# Nanocopter.net
KiCad netlist of a schematic drawn in EAGLE
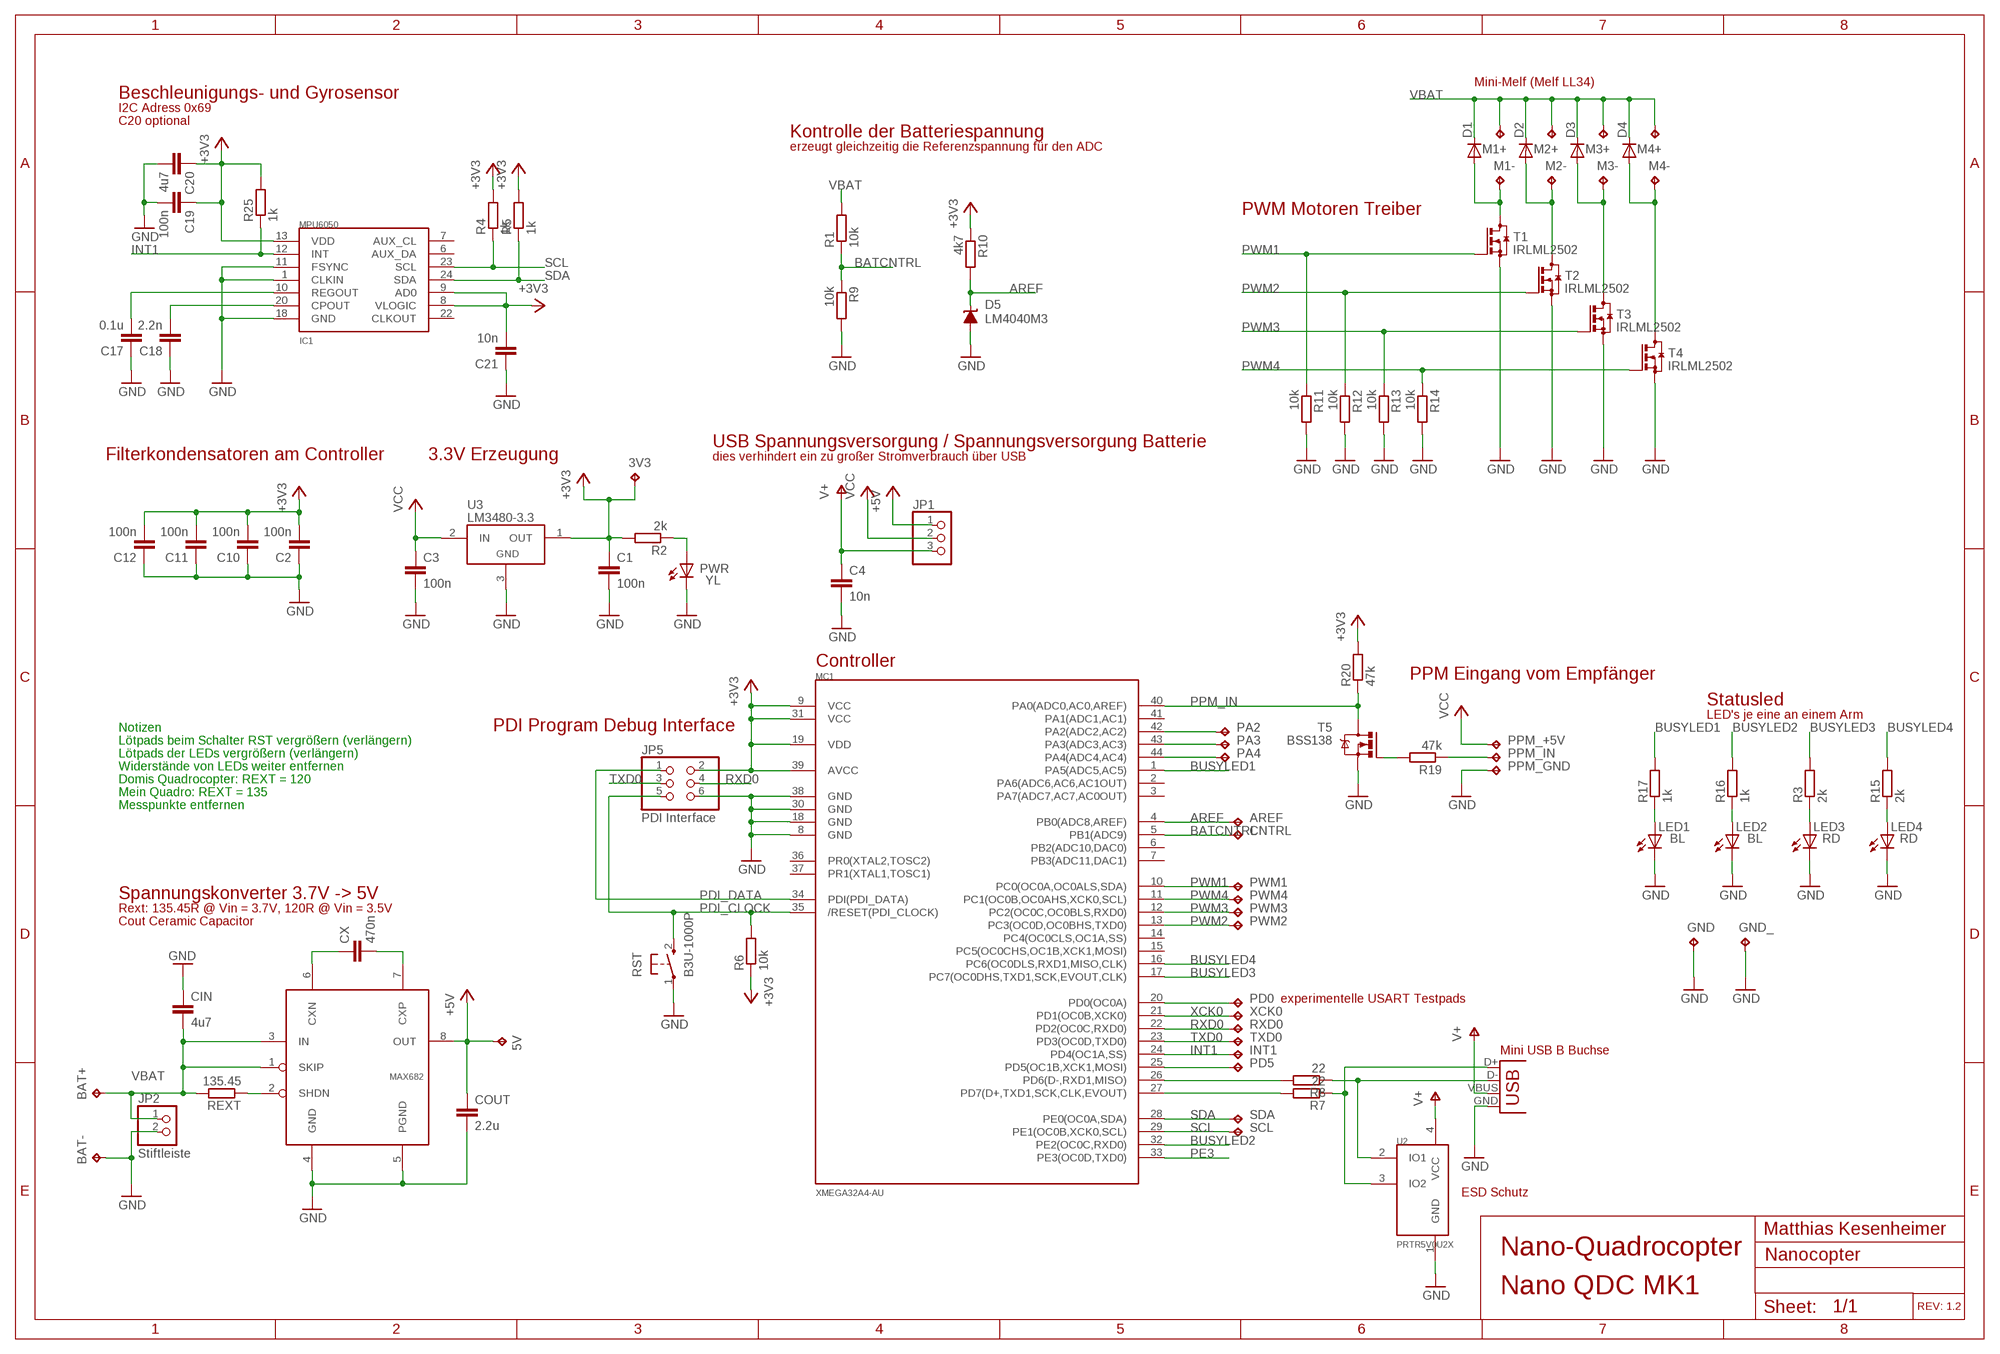
[diagram p0: schematic, sheet 1]

(export (version "E")
  (design (tool "Eeschema 10.0.6"))
  (components
    (comp (ref "3V3")
      (value "TPTP12SQ")
      (footprint "eagle-import:TP12SQ")
      (libsource (lib "eagle-import") (part "TPTP12SQ"))
    )
    (comp (ref "5V")
      (value "TPTP12SQ")
      (footprint "eagle-import:TP12SQ")
      (libsource (lib "eagle-import") (part "TPTP12SQ"))
    )
    (comp (ref "AREF")
      (value "TPTP10SQ")
      (footprint "eagle-import:TP10SQ")
      (libsource (lib "eagle-import") (part "TPTP10SQ"))
    )
    (comp (ref "BAT+")
      (value "TPTP12SQ")
      (footprint "eagle-import:TP12SQ")
      (libsource (lib "eagle-import") (part "TPTP12SQ"))
    )
    (comp (ref "BAT-")
      (value "TPTP12SQ")
      (footprint "eagle-import:TP12SQ")
      (libsource (lib "eagle-import") (part "TPTP12SQ"))
    )
    (comp (ref "C1")
      (value "100n")
      (footprint "eagle-import:C0603")
      (libsource (lib "eagle-import") (part "C-EUC0603"))
    )
    (comp (ref "C2")
      (value "100n")
      (footprint "eagle-import:C0603")
      (libsource (lib "eagle-import") (part "C-EUC0603"))
    )
    (comp (ref "C3")
      (value "100n")
      (footprint "eagle-import:C0603")
      (libsource (lib "eagle-import") (part "C-EUC0603"))
    )
    (comp (ref "C4")
      (value "10n")
      (footprint "eagle-import:C0603")
      (libsource (lib "eagle-import") (part "C-EUC0603"))
    )
    (comp (ref "C10")
      (value "100n")
      (footprint "eagle-import:C0603")
      (libsource (lib "eagle-import") (part "C-EUC0603"))
    )
    (comp (ref "C11")
      (value "100n")
      (footprint "eagle-import:C0603")
      (libsource (lib "eagle-import") (part "C-EUC0603"))
    )
    (comp (ref "C12")
      (value "100n")
      (footprint "eagle-import:C0603")
      (libsource (lib "eagle-import") (part "C-EUC0603"))
    )
    (comp (ref "C17")
      (value "0.1u")
      (footprint "eagle-import:C0603")
      (libsource (lib "eagle-import") (part "C-EUC0603"))
    )
    (comp (ref "C18")
      (value "2.2n")
      (footprint "eagle-import:C0603")
      (libsource (lib "eagle-import") (part "C-EUC0603"))
    )
    (comp (ref "C19")
      (value "100n")
      (footprint "eagle-import:C0603")
      (libsource (lib "eagle-import") (part "C-EUC0603"))
    )
    (comp (ref "C20")
      (value "4u7")
      (footprint "eagle-import:C0603")
      (libsource (lib "eagle-import") (part "C-EUC0603"))
    )
    (comp (ref "C21")
      (value "10n")
      (footprint "eagle-import:C0603")
      (libsource (lib "eagle-import") (part "C-EUC0603"))
    )
    (comp (ref "CIN")
      (value "4u7")
      (footprint "eagle-import:C1206")
      (libsource (lib "eagle-import") (part "C-EUC1206"))
    )
    (comp (ref "CNTRL")
      (value "TPTP10SQ")
      (footprint "eagle-import:TP10SQ")
      (libsource (lib "eagle-import") (part "TPTP10SQ"))
    )
    (comp (ref "COUT")
      (value "2.2u")
      (footprint "eagle-import:C1206")
      (libsource (lib "eagle-import") (part "C-EUC1206"))
    )
    (comp (ref "CX")
      (value "470n")
      (footprint "eagle-import:C0603")
      (libsource (lib "eagle-import") (part "C-EUC0603"))
    )
    (comp (ref "D1")
      (value "DIODE-MINIMELF")
      (footprint "eagle-import:MINIMELF")
      (libsource (lib "eagle-import") (part "DIODE-MINIMELF"))
    )
    (comp (ref "D2")
      (value "DIODE-MINIMELF")
      (footprint "eagle-import:MINIMELF")
      (libsource (lib "eagle-import") (part "DIODE-MINIMELF"))
    )
    (comp (ref "D3")
      (value "DIODE-MINIMELF")
      (footprint "eagle-import:MINIMELF")
      (libsource (lib "eagle-import") (part "DIODE-MINIMELF"))
    )
    (comp (ref "D4")
      (value "DIODE-MINIMELF")
      (footprint "eagle-import:MINIMELF")
      (libsource (lib "eagle-import") (part "DIODE-MINIMELF"))
    )
    (comp (ref "D5")
      (value "LM4040M3")
      (footprint "eagle-import:SOT-23")
      (libsource (lib "eagle-import") (part "LM4040M3"))
    )
    (comp (ref "GND")
      (value "TPTP12SQ")
      (footprint "eagle-import:TP12SQ")
      (libsource (lib "eagle-import") (part "TPTP12SQ"))
    )
    (comp (ref "GND_")
      (value "TPTP12SQ")
      (footprint "eagle-import:TP12SQ")
      (libsource (lib "eagle-import") (part "TPTP12SQ"))
    )
    (comp (ref "IC1")
      (value "MPU6050")
      (footprint "eagle-import:QFN-24")
      (libsource (lib "eagle-import") (part "MPU6050"))
    )
    (comp (ref "INT1")
      (value "TPTP10SQ")
      (footprint "eagle-import:TP10SQ")
      (libsource (lib "eagle-import") (part "TPTP10SQ"))
    )
    (comp (ref "JP1")
      (value "PINHD-1X3")
      (footprint "eagle-import:1X03")
      (libsource (lib "eagle-import") (part "PINHD-1X3"))
    )
    (comp (ref "JP2")
      (value "Stiftleiste")
      (footprint "eagle-import:1X02")
      (libsource (lib "eagle-import") (part "PINHD-1X2"))
    )
    (comp (ref "JP5")
      (value "PDI Interface")
      (footprint "eagle-import:2X03")
      (libsource (lib "eagle-import") (part "PINHD-2X3"))
    )
    (comp (ref "LED1")
      (value "BL")
      (footprint "eagle-import:CHIPLED_0603")
      (libsource (lib "eagle-import") (part "LEDCHIPLED_0603"))
    )
    (comp (ref "LED2")
      (value "BL")
      (footprint "eagle-import:CHIPLED_0603")
      (libsource (lib "eagle-import") (part "LEDCHIPLED_0603"))
    )
    (comp (ref "LED3")
      (value "RD")
      (footprint "eagle-import:CHIPLED_0603")
      (libsource (lib "eagle-import") (part "LEDCHIPLED_0603"))
    )
    (comp (ref "LED4")
      (value "RD")
      (footprint "eagle-import:CHIPLED_0603")
      (libsource (lib "eagle-import") (part "LEDCHIPLED_0603"))
    )
    (comp (ref "M1+")
      (value "TPTP15SQ")
      (footprint "eagle-import:TP15SQ")
      (libsource (lib "eagle-import") (part "TPTP15SQ"))
    )
    (comp (ref "M1-")
      (value "TPTP15SQ")
      (footprint "eagle-import:TP15SQ")
      (libsource (lib "eagle-import") (part "TPTP15SQ"))
    )
    (comp (ref "M2+")
      (value "TPTP15SQ")
      (footprint "eagle-import:TP15SQ")
      (libsource (lib "eagle-import") (part "TPTP15SQ"))
    )
    (comp (ref "M2-")
      (value "TPTP15SQ")
      (footprint "eagle-import:TP15SQ")
      (libsource (lib "eagle-import") (part "TPTP15SQ"))
    )
    (comp (ref "M3+")
      (value "TPTP15SQ")
      (footprint "eagle-import:TP15SQ")
      (libsource (lib "eagle-import") (part "TPTP15SQ"))
    )
    (comp (ref "M3-")
      (value "TPTP15SQ")
      (footprint "eagle-import:TP15SQ")
      (libsource (lib "eagle-import") (part "TPTP15SQ"))
    )
    (comp (ref "M4+")
      (value "TPTP15SQ")
      (footprint "eagle-import:TP15SQ")
      (libsource (lib "eagle-import") (part "TPTP15SQ"))
    )
    (comp (ref "M4-")
      (value "TPTP15SQ")
      (footprint "eagle-import:TP15SQ")
      (libsource (lib "eagle-import") (part "TPTP15SQ"))
    )
    (comp (ref "MC1")
      (value "XMEGA32A4-AU")
      (footprint "eagle-import:TQFP44")
      (libsource (lib "eagle-import") (part "XMEGA32A4-AU"))
    )
    (comp (ref "PA2")
      (value "TPTP10SQ")
      (footprint "eagle-import:TP10SQ")
      (libsource (lib "eagle-import") (part "TPTP10SQ"))
    )
    (comp (ref "PA3")
      (value "TPTP10SQ")
      (footprint "eagle-import:TP10SQ")
      (libsource (lib "eagle-import") (part "TPTP10SQ"))
    )
    (comp (ref "PA4")
      (value "TPTP10SQ")
      (footprint "eagle-import:TP10SQ")
      (libsource (lib "eagle-import") (part "TPTP10SQ"))
    )
    (comp (ref "PD0")
      (value "TPTP10SQ")
      (footprint "eagle-import:TP10SQ")
      (libsource (lib "eagle-import") (part "TPTP10SQ"))
    )
    (comp (ref "PD5")
      (value "TPTP10SQ")
      (footprint "eagle-import:TP10SQ")
      (libsource (lib "eagle-import") (part "TPTP10SQ"))
    )
    (comp (ref "PPM_+5V")
      (value "TPTP10SQ")
      (footprint "eagle-import:TP10SQ")
      (libsource (lib "eagle-import") (part "TPTP10SQ"))
    )
    (comp (ref "PPM_GND")
      (value "TPTP10SQ")
      (footprint "eagle-import:TP10SQ")
      (libsource (lib "eagle-import") (part "TPTP10SQ"))
    )
    (comp (ref "PPM_IN")
      (value "TPTP10SQ")
      (footprint "eagle-import:TP10SQ")
      (libsource (lib "eagle-import") (part "TPTP10SQ"))
    )
    (comp (ref "PWM1")
      (value "TPTP10SQ")
      (footprint "eagle-import:TP10SQ")
      (libsource (lib "eagle-import") (part "TPTP10SQ"))
    )
    (comp (ref "PWM2")
      (value "TPTP10SQ")
      (footprint "eagle-import:TP10SQ")
      (libsource (lib "eagle-import") (part "TPTP10SQ"))
    )
    (comp (ref "PWM3")
      (value "TPTP10SQ")
      (footprint "eagle-import:TP10SQ")
      (libsource (lib "eagle-import") (part "TPTP10SQ"))
    )
    (comp (ref "PWM4")
      (value "TPTP10SQ")
      (footprint "eagle-import:TP10SQ")
      (libsource (lib "eagle-import") (part "TPTP10SQ"))
    )
    (comp (ref "PWR")
      (value "YL")
      (footprint "eagle-import:CHIPLED_0603")
      (libsource (lib "eagle-import") (part "LEDCHIPLED_0603"))
    )
    (comp (ref "R1")
      (value "10k")
      (footprint "eagle-import:R0603")
      (libsource (lib "eagle-import") (part "R-EU_R0603"))
    )
    (comp (ref "R2")
      (value "2k")
      (footprint "eagle-import:R0603")
      (libsource (lib "eagle-import") (part "R-EU_R0603"))
    )
    (comp (ref "R3")
      (value "2k")
      (footprint "eagle-import:R0603")
      (libsource (lib "eagle-import") (part "R-EU_R0603"))
    )
    (comp (ref "R4")
      (value "1k")
      (footprint "eagle-import:R0603")
      (libsource (lib "eagle-import") (part "R-EU_R0603"))
    )
    (comp (ref "R5")
      (value "1k")
      (footprint "eagle-import:R0603")
      (libsource (lib "eagle-import") (part "R-EU_R0603"))
    )
    (comp (ref "R6")
      (value "10k")
      (footprint "eagle-import:R0603")
      (libsource (lib "eagle-import") (part "R-EU_R0603"))
    )
    (comp (ref "R7")
      (value "22")
      (footprint "eagle-import:R0603")
      (libsource (lib "eagle-import") (part "R-EU_R0603"))
    )
    (comp (ref "R8")
      (value "22")
      (footprint "eagle-import:R0603")
      (libsource (lib "eagle-import") (part "R-EU_R0603"))
    )
    (comp (ref "R9")
      (value "10k")
      (footprint "eagle-import:R0603")
      (libsource (lib "eagle-import") (part "R-EU_R0603"))
    )
    (comp (ref "R10")
      (value "4k7")
      (footprint "eagle-import:R0603")
      (libsource (lib "eagle-import") (part "R-EU_R0603"))
    )
    (comp (ref "R11")
      (value "10k")
      (footprint "eagle-import:R0603")
      (libsource (lib "eagle-import") (part "R-EU_R0603"))
    )
    (comp (ref "R12")
      (value "10k")
      (footprint "eagle-import:R0603")
      (libsource (lib "eagle-import") (part "R-EU_R0603"))
    )
    (comp (ref "R13")
      (value "10k")
      (footprint "eagle-import:R0603")
      (libsource (lib "eagle-import") (part "R-EU_R0603"))
    )
    (comp (ref "R14")
      (value "10k")
      (footprint "eagle-import:R0603")
      (libsource (lib "eagle-import") (part "R-EU_R0603"))
    )
    (comp (ref "R15")
      (value "2k")
      (footprint "eagle-import:R0603")
      (libsource (lib "eagle-import") (part "R-EU_R0603"))
    )
    (comp (ref "R16")
      (value "1k")
      (footprint "eagle-import:R0603")
      (libsource (lib "eagle-import") (part "R-EU_R0603"))
    )
    (comp (ref "R17")
      (value "1k")
      (footprint "eagle-import:R0603")
      (libsource (lib "eagle-import") (part "R-EU_R0603"))
    )
    (comp (ref "R19")
      (value "47k")
      (footprint "eagle-import:R0603")
      (libsource (lib "eagle-import") (part "R-EU_R0603"))
    )
    (comp (ref "R20")
      (value "47k")
      (footprint "eagle-import:R0603")
      (libsource (lib "eagle-import") (part "R-EU_R0603"))
    )
    (comp (ref "R25")
      (value "1k")
      (footprint "eagle-import:R0603")
      (libsource (lib "eagle-import") (part "R-EU_R0603"))
    )
    (comp (ref "REXT")
      (value "135.45")
      (footprint "eagle-import:R0603")
      (libsource (lib "eagle-import") (part "R-EU_R0603"))
    )
    (comp (ref "RST")
      (value "B3U-1000P")
      (footprint "eagle-import:SW_SMD")
      (libsource (lib "eagle-import") (part "B3U-1000P"))
    )
    (comp (ref "RXD0")
      (value "TPTP10SQ")
      (footprint "eagle-import:TP10SQ")
      (libsource (lib "eagle-import") (part "TPTP10SQ"))
    )
    (comp (ref "SCL")
      (value "TPTP10SQ")
      (footprint "eagle-import:TP10SQ")
      (libsource (lib "eagle-import") (part "TPTP10SQ"))
    )
    (comp (ref "SDA")
      (value "TPTP10SQ")
      (footprint "eagle-import:TP10SQ")
      (libsource (lib "eagle-import") (part "TPTP10SQ"))
    )
    (comp (ref "T1")
      (value "IRLML2502")
      (footprint "eagle-import:SOT23")
      (libsource (lib "eagle-import") (part "BSS123"))
    )
    (comp (ref "T2")
      (value "IRLML2502")
      (footprint "eagle-import:SOT23")
      (libsource (lib "eagle-import") (part "BSS123"))
    )
    (comp (ref "T3")
      (value "IRLML2502")
      (footprint "eagle-import:SOT23")
      (libsource (lib "eagle-import") (part "BSS123"))
    )
    (comp (ref "T4")
      (value "IRLML2502")
      (footprint "eagle-import:SOT23")
      (libsource (lib "eagle-import") (part "BSS123"))
    )
    (comp (ref "T5")
      (value "BSS138")
      (footprint "eagle-import:SOT23")
      (libsource (lib "eagle-import") (part "BSS138"))
    )
    (comp (ref "TXD0")
      (value "TPTP10SQ")
      (footprint "eagle-import:TP10SQ")
      (libsource (lib "eagle-import") (part "TPTP10SQ"))
    )
    (comp (ref "U1")
      (value "MAX682")
      (footprint "eagle-import:SOIC(N)8")
      (libsource (lib "eagle-import") (part "MAX682"))
    )
    (comp (ref "U2")
      (value "PRTR5V0U2X")
      (footprint "eagle-import:SOT143B")
      (libsource (lib "eagle-import") (part "PRTR5V0U2X"))
    )
    (comp (ref "U3")
      (value "LM3480-3.3")
      (footprint "eagle-import:SOT-23-3")
      (libsource (lib "eagle-import") (part "LM3480-3.3"))
    )
    (comp (ref "X1")
      (value "USBSMD")
      (footprint "eagle-import:USB-MINIB")
      (libsource (lib "eagle-import") (part "USBSMD"))
    )
    (comp (ref "XCK0")
      (value "TPTP10SQ")
      (footprint "eagle-import:TP10SQ")
      (libsource (lib "eagle-import") (part "TPTP10SQ"))
    )
  )
  (nets
    (net (code "1") (name "+3V3") (class "Default")
      (node (ref "3V3") (pin "TP") (pinfunction "TP_TP") (pintype "input"))
      (node (ref "C1") (pin "1") (pinfunction "1_1") (pintype "passive"))
      (node (ref "C10") (pin "2") (pinfunction "2_2") (pintype "passive"))
      (node (ref "C11") (pin "2") (pinfunction "2_2") (pintype "passive"))
      (node (ref "C12") (pin "2") (pinfunction "2_2") (pintype "passive"))
      (node (ref "C19") (pin "1") (pinfunction "1_1") (pintype "passive"))
      (node (ref "C2") (pin "2") (pinfunction "2_2") (pintype "passive"))
      (node (ref "C20") (pin "1") (pinfunction "1_1") (pintype "passive"))
      (node (ref "C21") (pin "2") (pinfunction "2_2") (pintype "passive"))
      (node (ref "IC1") (pin "13") (pinfunction "VDD_13") (pintype "power_in"))
      (node (ref "IC1") (pin "8") (pinfunction "VLOGIC_8") (pintype "power_in"))
      (node (ref "IC1") (pin "9") (pinfunction "AD0_9") (pintype "input"))
      (node (ref "JP5") (pin "2") (pinfunction "2_2") (pintype "passive"))
      (node (ref "MC1") (pin "19") (pinfunction "VDD_19") (pintype "power_in"))
      (node (ref "MC1") (pin "31") (pinfunction "VCC_31") (pintype "power_in"))
      (node (ref "MC1") (pin "39") (pinfunction "AVCC_39") (pintype "power_in"))
      (node (ref "MC1") (pin "9") (pinfunction "VCC_9") (pintype "power_in"))
      (node (ref "R10") (pin "1") (pinfunction "1_1") (pintype "passive"))
      (node (ref "R2") (pin "2") (pinfunction "2_2") (pintype "passive"))
      (node (ref "R20") (pin "2") (pinfunction "2_2") (pintype "passive"))
      (node (ref "R25") (pin "2") (pinfunction "2_2") (pintype "passive"))
      (node (ref "R4") (pin "2") (pinfunction "2_2") (pintype "passive"))
      (node (ref "R5") (pin "2") (pinfunction "2_2") (pintype "passive"))
      (node (ref "R6") (pin "1") (pinfunction "1_1") (pintype "passive"))
      (node (ref "U3") (pin "1") (pinfunction "OUT_1") (pintype "power_in"))
    )
    (net (code "2") (name "+5V") (class "Default")
      (node (ref "5V") (pin "TP") (pinfunction "TP_TP") (pintype "input"))
      (node (ref "COUT") (pin "1") (pinfunction "1_1") (pintype "passive"))
      (node (ref "JP1") (pin "1") (pinfunction "1_1") (pintype "passive"))
      (node (ref "U1") (pin "8") (pinfunction "OUT_8") (pintype "power_in"))
    )
    (net (code "3") (name "/AREF") (class "Default")
      (node (ref "AREF") (pin "TP") (pinfunction "TP_TP") (pintype "input"))
      (node (ref "D5") (pin "1") (pinfunction "C_1") (pintype "passive"))
      (node (ref "MC1") (pin "4") (pinfunction "PB0(ADC8,AREF)_4") (pintype "bidirectional"))
      (node (ref "R10") (pin "2") (pinfunction "2_2") (pintype "passive"))
    )
    (net (code "4") (name "/BATCNTRL") (class "Default")
      (node (ref "CNTRL") (pin "TP") (pinfunction "TP_TP") (pintype "input"))
      (node (ref "MC1") (pin "5") (pinfunction "PB1(ADC9)_5") (pintype "bidirectional"))
      (node (ref "R1") (pin "1") (pinfunction "1_1") (pintype "passive"))
      (node (ref "R9") (pin "1") (pinfunction "1_1") (pintype "passive"))
    )
    (net (code "5") (name "/BUSYLED1") (class "Default")
      (node (ref "MC1") (pin "1") (pinfunction "PA5(ADC5,AC5)_1") (pintype "bidirectional"))
      (node (ref "R17") (pin "2") (pinfunction "2_2") (pintype "passive"))
    )
    (net (code "6") (name "/BUSYLED2") (class "Default")
      (node (ref "MC1") (pin "32") (pinfunction "PE2(OC0C,RXD0)_32") (pintype "bidirectional"))
      (node (ref "R16") (pin "2") (pinfunction "2_2") (pintype "passive"))
    )
    (net (code "7") (name "/BUSYLED3") (class "Default")
      (node (ref "MC1") (pin "17") (pinfunction "PC7(OC0DHS,TXD1,SCK,EVOUT,CLK)_17") (pintype "bidirectional"))
      (node (ref "R3") (pin "2") (pinfunction "2_2") (pintype "passive"))
    )
    (net (code "8") (name "/BUSYLED4") (class "Default")
      (node (ref "MC1") (pin "16") (pinfunction "PC6(OC0DLS,RXD1,MISO,CLK)_16") (pintype "bidirectional"))
      (node (ref "R15") (pin "2") (pinfunction "2_2") (pintype "passive"))
    )
    (net (code "9") (name "/INT1") (class "Default")
      (node (ref "IC1") (pin "12") (pinfunction "INT_12") (pintype "output"))
      (node (ref "INT1") (pin "TP") (pinfunction "TP_TP") (pintype "input"))
      (node (ref "MC1") (pin "24") (pinfunction "PD4(OC1A,SS)_24") (pintype "bidirectional"))
      (node (ref "R25") (pin "1") (pinfunction "1_1") (pintype "passive"))
    )
    (net (code "10") (name "/PDI_CLOCK") (class "Default")
      (node (ref "JP5") (pin "5") (pinfunction "5_5") (pintype "passive"))
      (node (ref "MC1") (pin "35") (pinfunction "/RESET(PDI_CLOCK)_35") (pintype "bidirectional"))
      (node (ref "R6") (pin "2") (pinfunction "2_2") (pintype "passive"))
      (node (ref "RST") (pin "2") (pinfunction "2_2") (pintype "passive"))
    )
    (net (code "11") (name "/PDI_DATA") (class "Default")
      (node (ref "JP5") (pin "1") (pinfunction "1_1") (pintype "passive"))
      (node (ref "MC1") (pin "34") (pinfunction "PDI(PDI_DATA)_34") (pintype "bidirectional"))
    )
    (net (code "12") (name "/PE3") (class "Default")
      (node (ref "MC1") (pin "33") (pinfunction "PE3(OC0D,TXD0)_33") (pintype "bidirectional"))
    )
    (net (code "13") (name "/PPM_IN") (class "Default")
      (node (ref "MC1") (pin "40") (pinfunction "PA0(ADC0,AC0,AREF)_40") (pintype "bidirectional"))
      (node (ref "R20") (pin "1") (pinfunction "1_1") (pintype "passive"))
      (node (ref "T5") (pin "3") (pinfunction "D_3") (pintype "passive"))
    )
    (net (code "14") (name "/PWM1") (class "Default")
      (node (ref "MC1") (pin "10") (pinfunction "PC0(OC0A,OC0ALS,SDA)_10") (pintype "bidirectional"))
      (node (ref "PWM1") (pin "TP") (pinfunction "TP_TP") (pintype "input"))
      (node (ref "R11") (pin "1") (pinfunction "1_1") (pintype "passive"))
      (node (ref "T1") (pin "1") (pinfunction "G_1") (pintype "passive"))
    )
    (net (code "15") (name "/PWM2") (class "Default")
      (node (ref "MC1") (pin "13") (pinfunction "PC3(OC0D,OC0BHS,TXD0)_13") (pintype "bidirectional"))
      (node (ref "PWM2") (pin "TP") (pinfunction "TP_TP") (pintype "input"))
      (node (ref "R12") (pin "1") (pinfunction "1_1") (pintype "passive"))
      (node (ref "T2") (pin "1") (pinfunction "G_1") (pintype "passive"))
    )
    (net (code "16") (name "/PWM3") (class "Default")
      (node (ref "MC1") (pin "12") (pinfunction "PC2(OC0C,OC0BLS,RXD0)_12") (pintype "bidirectional"))
      (node (ref "PWM3") (pin "TP") (pinfunction "TP_TP") (pintype "input"))
      (node (ref "R13") (pin "1") (pinfunction "1_1") (pintype "passive"))
      (node (ref "T3") (pin "1") (pinfunction "G_1") (pintype "passive"))
    )
    (net (code "17") (name "/PWM4") (class "Default")
      (node (ref "MC1") (pin "11") (pinfunction "PC1(OC0B,OC0AHS,XCK0,SCL)_11") (pintype "bidirectional"))
      (node (ref "PWM4") (pin "TP") (pinfunction "TP_TP") (pintype "input"))
      (node (ref "R14") (pin "1") (pinfunction "1_1") (pintype "passive"))
      (node (ref "T4") (pin "1") (pinfunction "G_1") (pintype "passive"))
    )
    (net (code "18") (name "/RXD0") (class "Default")
      (node (ref "JP5") (pin "4") (pinfunction "4_4") (pintype "passive"))
      (node (ref "MC1") (pin "22") (pinfunction "PD2(OC0C,RXD0)_22") (pintype "bidirectional"))
      (node (ref "RXD0") (pin "TP") (pinfunction "TP_TP") (pintype "input"))
    )
    (net (code "19") (name "/SCL") (class "Default")
      (node (ref "IC1") (pin "23") (pinfunction "SCL_23") (pintype "input"))
      (node (ref "MC1") (pin "29") (pinfunction "PE1(OC0B,XCK0,SCL)_29") (pintype "bidirectional"))
      (node (ref "R4") (pin "1") (pinfunction "1_1") (pintype "passive"))
      (node (ref "SCL") (pin "TP") (pinfunction "TP_TP") (pintype "input"))
    )
    (net (code "20") (name "/SDA") (class "Default")
      (node (ref "IC1") (pin "24") (pinfunction "SDA_24") (pintype "bidirectional"))
      (node (ref "MC1") (pin "28") (pinfunction "PE0(OC0A,SDA)_28") (pintype "bidirectional"))
      (node (ref "R5") (pin "1") (pinfunction "1_1") (pintype "passive"))
      (node (ref "SDA") (pin "TP") (pinfunction "TP_TP") (pintype "input"))
    )
    (net (code "21") (name "/TXD0") (class "Default")
      (node (ref "JP5") (pin "3") (pinfunction "3_3") (pintype "passive"))
      (node (ref "MC1") (pin "23") (pinfunction "PD3(OC0D,TXD0)_23") (pintype "bidirectional"))
      (node (ref "TXD0") (pin "TP") (pinfunction "TP_TP") (pintype "input"))
    )
    (net (code "22") (name "/VBAT") (class "Default")
      (node (ref "BAT+") (pin "TP") (pinfunction "TP_TP") (pintype "input"))
      (node (ref "CIN") (pin "2") (pinfunction "2_2") (pintype "passive"))
      (node (ref "D1") (pin "C") (pinfunction "C_C") (pintype "passive"))
      (node (ref "D2") (pin "C") (pinfunction "C_C") (pintype "passive"))
      (node (ref "D3") (pin "C") (pinfunction "C_C") (pintype "passive"))
      (node (ref "D4") (pin "C") (pinfunction "C_C") (pintype "passive"))
      (node (ref "JP2") (pin "1") (pinfunction "1_1") (pintype "passive"))
      (node (ref "M1+") (pin "TP") (pinfunction "TP_TP") (pintype "input"))
      (node (ref "M2+") (pin "TP") (pinfunction "TP_TP") (pintype "input"))
      (node (ref "M3+") (pin "TP") (pinfunction "TP_TP") (pintype "input"))
      (node (ref "M4+") (pin "TP") (pinfunction "TP_TP") (pintype "input"))
      (node (ref "R1") (pin "2") (pinfunction "2_2") (pintype "passive"))
      (node (ref "REXT") (pin "2") (pinfunction "2_2") (pintype "passive"))
      (node (ref "U1") (pin "1") (pinfunction "SKIP_1") (pintype "input"))
      (node (ref "U1") (pin "3") (pinfunction "IN_3") (pintype "input"))
    )
    (net (code "23") (name "/XCK0") (class "Default")
      (node (ref "MC1") (pin "21") (pinfunction "PD1(OC0B,XCK0)_21") (pintype "bidirectional"))
      (node (ref "XCK0") (pin "TP") (pinfunction "TP_TP") (pintype "input"))
    )
    (net (code "24") (name "GND") (class "Default")
      (node (ref "BAT-") (pin "TP") (pinfunction "TP_TP") (pintype "input"))
      (node (ref "C1") (pin "2") (pinfunction "2_2") (pintype "passive"))
      (node (ref "C10") (pin "1") (pinfunction "1_1") (pintype "passive"))
      (node (ref "C11") (pin "1") (pinfunction "1_1") (pintype "passive"))
      (node (ref "C12") (pin "1") (pinfunction "1_1") (pintype "passive"))
      (node (ref "C17") (pin "1") (pinfunction "1_1") (pintype "passive"))
      (node (ref "C18") (pin "1") (pinfunction "1_1") (pintype "passive"))
      (node (ref "C19") (pin "2") (pinfunction "2_2") (pintype "passive"))
      (node (ref "C2") (pin "1") (pinfunction "1_1") (pintype "passive"))
      (node (ref "C20") (pin "2") (pinfunction "2_2") (pintype "passive"))
      (node (ref "C21") (pin "1") (pinfunction "1_1") (pintype "passive"))
      (node (ref "C3") (pin "2") (pinfunction "2_2") (pintype "passive"))
      (node (ref "C4") (pin "2") (pinfunction "2_2") (pintype "passive"))
      (node (ref "CIN") (pin "1") (pinfunction "1_1") (pintype "passive"))
      (node (ref "COUT") (pin "2") (pinfunction "2_2") (pintype "passive"))
      (node (ref "D5") (pin "2") (pinfunction "A_2") (pintype "passive"))
      (node (ref "GND") (pin "TP") (pinfunction "TP_TP") (pintype "input"))
      (node (ref "GND_") (pin "TP") (pinfunction "TP_TP") (pintype "input"))
      (node (ref "IC1") (pin "1") (pinfunction "CLKIN_1") (pintype "input"))
      (node (ref "IC1") (pin "11") (pinfunction "FSYNC_11") (pintype "input"))
      (node (ref "IC1") (pin "18") (pinfunction "GND_18") (pintype "power_in"))
      (node (ref "JP2") (pin "2") (pinfunction "2_2") (pintype "passive"))
      (node (ref "JP5") (pin "6") (pinfunction "6_6") (pintype "passive"))
      (node (ref "LED1") (pin "C") (pinfunction "C_C") (pintype "passive"))
      (node (ref "LED2") (pin "C") (pinfunction "C_C") (pintype "passive"))
      (node (ref "LED3") (pin "C") (pinfunction "C_C") (pintype "passive"))
      (node (ref "LED4") (pin "C") (pinfunction "C_C") (pintype "passive"))
      (node (ref "MC1") (pin "18") (pinfunction "GND_18") (pintype "power_in"))
      (node (ref "MC1") (pin "30") (pinfunction "GND_30") (pintype "power_in"))
      (node (ref "MC1") (pin "38") (pinfunction "GND_38") (pintype "power_in"))
      (node (ref "MC1") (pin "8") (pinfunction "GND_8") (pintype "power_in"))
      (node (ref "PPM_GND") (pin "TP") (pinfunction "TP_TP") (pintype "input"))
      (node (ref "PWR") (pin "C") (pinfunction "C_C") (pintype "passive"))
      (node (ref "R11") (pin "2") (pinfunction "2_2") (pintype "passive"))
      (node (ref "R12") (pin "2") (pinfunction "2_2") (pintype "passive"))
      (node (ref "R13") (pin "2") (pinfunction "2_2") (pintype "passive"))
      (node (ref "R14") (pin "2") (pinfunction "2_2") (pintype "passive"))
      (node (ref "R9") (pin "2") (pinfunction "2_2") (pintype "passive"))
      (node (ref "RST") (pin "1") (pinfunction "1_1") (pintype "passive"))
      (node (ref "T1") (pin "2") (pinfunction "S_2") (pintype "passive"))
      (node (ref "T2") (pin "2") (pinfunction "S_2") (pintype "passive"))
      (node (ref "T3") (pin "2") (pinfunction "S_2") (pintype "passive"))
      (node (ref "T4") (pin "2") (pinfunction "S_2") (pintype "passive"))
      (node (ref "T5") (pin "2") (pinfunction "S_2") (pintype "passive"))
      (node (ref "U1") (pin "4") (pinfunction "GND_4") (pintype "power_in"))
      (node (ref "U1") (pin "5") (pinfunction "PGND_5") (pintype "power_in"))
      (node (ref "U2") (pin "1") (pinfunction "GND_1") (pintype "power_in"))
      (node (ref "U3") (pin "3") (pinfunction "GND_3") (pintype "power_in"))
      (node (ref "X1") (pin "GND") (pinfunction "GND_GND") (pintype "bidirectional"))
    )
    (net (code "25") (name "Net-(IC1-CPOUT)") (class "Default")
      (node (ref "C18") (pin "2") (pinfunction "2_2") (pintype "passive"))
      (node (ref "IC1") (pin "20") (pinfunction "CPOUT_20") (pintype "output"))
    )
    (net (code "26") (name "Net-(IC1-REGOUT)") (class "Default")
      (node (ref "C17") (pin "2") (pinfunction "2_2") (pintype "passive"))
      (node (ref "IC1") (pin "10") (pinfunction "REGOUT_10") (pintype "output"))
    )
    (net (code "27") (name "Net-(LED1-PadA)") (class "Default")
      (node (ref "LED1") (pin "A") (pinfunction "A_A") (pintype "passive"))
      (node (ref "R17") (pin "1") (pinfunction "1_1") (pintype "passive"))
    )
    (net (code "28") (name "Net-(LED2-PadA)") (class "Default")
      (node (ref "LED2") (pin "A") (pinfunction "A_A") (pintype "passive"))
      (node (ref "R16") (pin "1") (pinfunction "1_1") (pintype "passive"))
    )
    (net (code "29") (name "Net-(LED3-PadA)") (class "Default")
      (node (ref "LED3") (pin "A") (pinfunction "A_A") (pintype "passive"))
      (node (ref "R3") (pin "1") (pinfunction "1_1") (pintype "passive"))
    )
    (net (code "30") (name "Net-(LED4-PadA)") (class "Default")
      (node (ref "LED4") (pin "A") (pinfunction "A_A") (pintype "passive"))
      (node (ref "R15") (pin "1") (pinfunction "1_1") (pintype "passive"))
    )
    (net (code "31") (name "Net-(MC1-PA2(ADC2,AC2))") (class "Default")
      (node (ref "MC1") (pin "42") (pinfunction "PA2(ADC2,AC2)_42") (pintype "bidirectional"))
      (node (ref "PA2") (pin "TP") (pinfunction "TP_TP") (pintype "input"))
    )
    (net (code "32") (name "Net-(MC1-PA3(ADC3,AC3))") (class "Default")
      (node (ref "MC1") (pin "43") (pinfunction "PA3(ADC3,AC3)_43") (pintype "bidirectional"))
      (node (ref "PA3") (pin "TP") (pinfunction "TP_TP") (pintype "input"))
    )
    (net (code "33") (name "Net-(MC1-PA4(ADC4,AC4))") (class "Default")
      (node (ref "MC1") (pin "44") (pinfunction "PA4(ADC4,AC4)_44") (pintype "bidirectional"))
      (node (ref "PA4") (pin "TP") (pinfunction "TP_TP") (pintype "input"))
    )
    (net (code "34") (name "Net-(MC1-PD0(OC0A))") (class "Default")
      (node (ref "MC1") (pin "20") (pinfunction "PD0(OC0A)_20") (pintype "bidirectional"))
      (node (ref "PD0") (pin "TP") (pinfunction "TP_TP") (pintype "input"))
    )
    (net (code "35") (name "Net-(MC1-PD5(OC1B,XCK1,MOSI))") (class "Default")
      (node (ref "MC1") (pin "25") (pinfunction "PD5(OC1B,XCK1,MOSI)_25") (pintype "bidirectional"))
      (node (ref "PD5") (pin "TP") (pinfunction "TP_TP") (pintype "input"))
    )
    (net (code "36") (name "Net-(MC1-PD6(D-,RXD1,MISO))") (class "Default")
      (node (ref "MC1") (pin "26") (pinfunction "PD6(D-,RXD1,MISO)_26") (pintype "bidirectional"))
      (node (ref "R8") (pin "2") (pinfunction "2_2") (pintype "passive"))
    )
    (net (code "37") (name "Net-(MC1-PD7(D+,TXD1,SCK,CLK,EVOUT))") (class "Default")
      (node (ref "MC1") (pin "27") (pinfunction "PD7(D+,TXD1,SCK,CLK,EVOUT)_27") (pintype "bidirectional"))
      (node (ref "R7") (pin "2") (pinfunction "2_2") (pintype "passive"))
    )
    (net (code "38") (name "Net-(PPM_IN-PadTP)") (class "Default")
      (node (ref "PPM_IN") (pin "TP") (pinfunction "TP_TP") (pintype "input"))
      (node (ref "R19") (pin "1") (pinfunction "1_1") (pintype "passive"))
    )
    (net (code "39") (name "Net-(PWR-PadA)") (class "Default")
      (node (ref "PWR") (pin "A") (pinfunction "A_A") (pintype "passive"))
      (node (ref "R2") (pin "1") (pinfunction "1_1") (pintype "passive"))
    )
    (net (code "40") (name "Net-(T1-D)") (class "Default")
      (node (ref "D1") (pin "A") (pinfunction "A_A") (pintype "passive"))
      (node (ref "M1-") (pin "TP") (pinfunction "TP_TP") (pintype "input"))
      (node (ref "T1") (pin "3") (pinfunction "D_3") (pintype "passive"))
    )
    (net (code "41") (name "Net-(T2-D)") (class "Default")
      (node (ref "D2") (pin "A") (pinfunction "A_A") (pintype "passive"))
      (node (ref "M2-") (pin "TP") (pinfunction "TP_TP") (pintype "input"))
      (node (ref "T2") (pin "3") (pinfunction "D_3") (pintype "passive"))
    )
    (net (code "42") (name "Net-(T3-D)") (class "Default")
      (node (ref "D3") (pin "A") (pinfunction "A_A") (pintype "passive"))
      (node (ref "M3-") (pin "TP") (pinfunction "TP_TP") (pintype "input"))
      (node (ref "T3") (pin "3") (pinfunction "D_3") (pintype "passive"))
    )
    (net (code "43") (name "Net-(T4-D)") (class "Default")
      (node (ref "D4") (pin "A") (pinfunction "A_A") (pintype "passive"))
      (node (ref "M4-") (pin "TP") (pinfunction "TP_TP") (pintype "input"))
      (node (ref "T4") (pin "3") (pinfunction "D_3") (pintype "passive"))
    )
    (net (code "44") (name "Net-(T5-G)") (class "Default")
      (node (ref "R19") (pin "2") (pinfunction "2_2") (pintype "passive"))
      (node (ref "T5") (pin "1") (pinfunction "G_1") (pintype "passive"))
    )
    (net (code "45") (name "Net-(U1-CXN)") (class "Default")
      (node (ref "CX") (pin "1") (pinfunction "1_1") (pintype "passive"))
      (node (ref "U1") (pin "6") (pinfunction "CXN_6") (pintype "passive"))
    )
    (net (code "46") (name "Net-(U1-CXP)") (class "Default")
      (node (ref "CX") (pin "2") (pinfunction "2_2") (pintype "passive"))
      (node (ref "U1") (pin "7") (pinfunction "CXP_7") (pintype "passive"))
    )
    (net (code "47") (name "Net-(U1-SHDN)") (class "Default")
      (node (ref "REXT") (pin "1") (pinfunction "1_1") (pintype "passive"))
      (node (ref "U1") (pin "2") (pinfunction "SHDN_2") (pintype "input"))
    )
    (net (code "48") (name "Net-(U2-IO1)") (class "Default")
      (node (ref "R8") (pin "1") (pinfunction "1_1") (pintype "passive"))
      (node (ref "U2") (pin "2") (pinfunction "IO1_2") (pintype "bidirectional"))
      (node (ref "X1") (pin "D-") (pinfunction "D-_D-") (pintype "bidirectional"))
    )
    (net (code "49") (name "Net-(U2-IO2)") (class "Default")
      (node (ref "R7") (pin "1") (pinfunction "1_1") (pintype "passive"))
      (node (ref "U2") (pin "3") (pinfunction "IO2_3") (pintype "bidirectional"))
      (node (ref "X1") (pin "D+") (pinfunction "D+_D+") (pintype "bidirectional"))
    )
    (net (code "50") (name "V+") (class "Default")
      (node (ref "C4") (pin "1") (pinfunction "1_1") (pintype "passive"))
      (node (ref "JP1") (pin "3") (pinfunction "3_3") (pintype "passive"))
      (node (ref "U2") (pin "4") (pinfunction "VCC_4") (pintype "power_in"))
      (node (ref "X1") (pin "VBUS") (pinfunction "VBUS_VBUS") (pintype "bidirectional"))
    )
    (net (code "51") (name "VCC") (class "Default")
      (node (ref "C3") (pin "1") (pinfunction "1_1") (pintype "passive"))
      (node (ref "JP1") (pin "2") (pinfunction "2_2") (pintype "passive"))
      (node (ref "PPM_+5V") (pin "TP") (pinfunction "TP_TP") (pintype "input"))
      (node (ref "U3") (pin "2") (pinfunction "IN_2") (pintype "power_in"))
    )
    (net (code "52") (name "unconnected-(IC1-AUX_CL-Pad7)") (class "Default")
      (node (ref "IC1") (pin "7") (pinfunction "AUX_CL_7") (pintype "output"))
    )
    (net (code "53") (name "unconnected-(IC1-AUX_DA-Pad6)") (class "Default")
      (node (ref "IC1") (pin "6") (pinfunction "AUX_DA_6") (pintype "bidirectional"))
    )
    (net (code "54") (name "unconnected-(IC1-CLKOUT-Pad22)") (class "Default")
      (node (ref "IC1") (pin "22") (pinfunction "CLKOUT_22") (pintype "output"))
    )
    (net (code "55") (name "unconnected-(MC1-PA1(ADC1,AC1)-Pad41)") (class "Default")
      (node (ref "MC1") (pin "41") (pinfunction "PA1(ADC1,AC1)_41") (pintype "bidirectional"))
    )
    (net (code "56") (name "unconnected-(MC1-PA6(ADC6,AC6,AC1OUT)-Pad2)") (class "Default")
      (node (ref "MC1") (pin "2") (pinfunction "PA6(ADC6,AC6,AC1OUT)_2") (pintype "bidirectional"))
    )
    (net (code "57") (name "unconnected-(MC1-PA7(ADC7,AC7,AC0OUT)-Pad3)") (class "Default")
      (node (ref "MC1") (pin "3") (pinfunction "PA7(ADC7,AC7,AC0OUT)_3") (pintype "bidirectional"))
    )
    (net (code "58") (name "unconnected-(MC1-PB2(ADC10,DAC0)-Pad6)") (class "Default")
      (node (ref "MC1") (pin "6") (pinfunction "PB2(ADC10,DAC0)_6") (pintype "bidirectional"))
    )
    (net (code "59") (name "unconnected-(MC1-PB3(ADC11,DAC1)-Pad7)") (class "Default")
      (node (ref "MC1") (pin "7") (pinfunction "PB3(ADC11,DAC1)_7") (pintype "bidirectional"))
    )
    (net (code "60") (name "unconnected-(MC1-PC4(OC0CLS,OC1A,SS)-Pad14)") (class "Default")
      (node (ref "MC1") (pin "14") (pinfunction "PC4(OC0CLS,OC1A,SS)_14") (pintype "bidirectional"))
    )
    (net (code "61") (name "unconnected-(MC1-PC5(OC0CHS,OC1B,XCK1,MOSI)-Pad15)") (class "Default")
      (node (ref "MC1") (pin "15") (pinfunction "PC5(OC0CHS,OC1B,XCK1,MOSI)_15") (pintype "bidirectional"))
    )
    (net (code "62") (name "unconnected-(MC1-PR0(XTAL2,TOSC2)-Pad36)") (class "Default")
      (node (ref "MC1") (pin "36") (pinfunction "PR0(XTAL2,TOSC2)_36") (pintype "bidirectional"))
    )
    (net (code "63") (name "unconnected-(MC1-PR1(XTAL1,TOSC1)-Pad37)") (class "Default")
      (node (ref "MC1") (pin "37") (pinfunction "PR1(XTAL1,TOSC1)_37") (pintype "bidirectional"))
    )
  )
)
